# InclinometerDisplay.net
KiCad netlist of a schematic drawn in Altium Designer
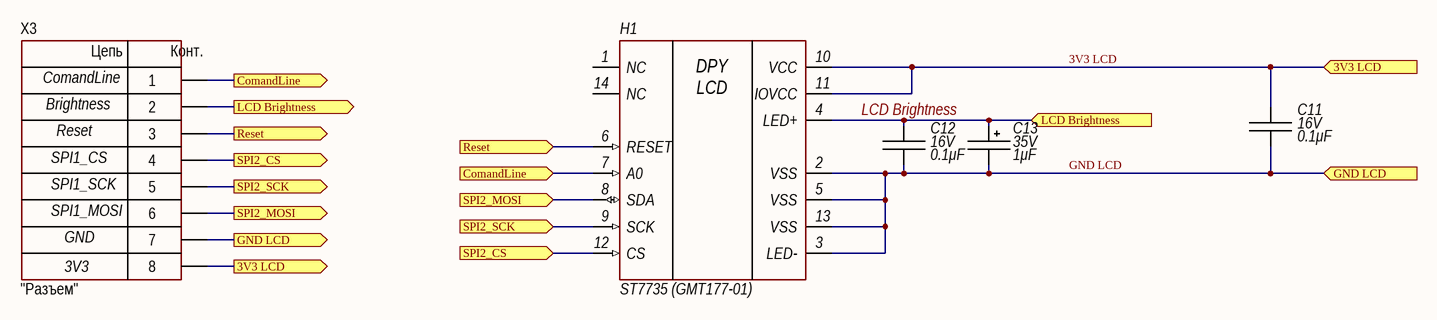
[diagram p0: InclinometerDisplay.SchDoc]

(export (version "E")
  (design (tool "Eeschema 10.0.6"))
  (components
    (comp (ref "C11")
      (value "0.1μF")
      (footprint "CAP: 0603")
      (fields
        (field (name "MANUFACTURER") "Murata Electronics")
        (field (name "PARTNUMBER") "GRM188R71C104KA01D")
        (field (name "VALUEMANUFACTURERPARTNUMBER") "Ceramic capacitor, 0.1μF, X7R, ±10%, 16V, 0603, -55...+125°C")
        (field (name "VOLTAGE") "16V")
      )
      (libsource (lib "Capacitor") (part "Ceramic_0603"))
    )
    (comp (ref "C12")
      (value "0.1μF")
      (footprint "CAP: 0603")
      (fields
        (field (name "MANUFACTURER") "Murata Electronics")
        (field (name "PARTNUMBER") "GRM188R71C104KA01D")
        (field (name "VALUEMANUFACTURERPARTNUMBER") "Ceramic capacitor, 0.1μF, X7R, ±10%, 16V, 0603, -55...+125°C")
        (field (name "VOLTAGE") "16V")
      )
      (libsource (lib "Capacitor") (part "Ceramic_0603"))
    )
    (comp (ref "C13")
      (value "1μF")
      (footprint "CAP: TANTAL-A")
      (fields
        (field (name "MANUFACTURER") "AVX")
        (field (name "PARTNUMBER") "TAJA105K035RNJ")
        (field (name "VALUEMANUFACTURERPARTNUMBER") "Tantalum capacitor, 1μF, 35V, ±10%, 7.5Ohm, case A (3216), -55...+125°C")
        (field (name "VOLTAGE") "35V")
      )
      (libsource (lib "Capacitor") (part "Tantal_A"))
    )
    (comp (ref "H1")
      (value "ST7735 (GMT177-01)")
      (footprint "ST7735 DISPLAY")
      (libsource (lib "Displays") (part "ST7735 DISPLAY"))
    )
    (comp (ref "X3")
      (value "~")
      (footprint "CON: PLS-8")
      (fields
        (field (name "MANUFACTURER") "Connfly")
        (field (name "VALUEMANUFACTURERPARTNUMBER") "Connector, 8pin, 2.54mm, 500VAC, 3A")
        (field (name "PARTNUMBER") "PLS-8")
        (field (name "COMMENTTEXT") "\"Разъем\"")
      )
      (libsource (lib "Connector") (part "PLS-8"))
    )
  )
  (nets
    (net (code "1") (name "/3V3 LCD") (class "Default")
      (node (ref "C11") (pin "2") (pinfunction "2_2") (pintype "power_in"))
      (node (ref "H1") (pin "10") (pinfunction "VCC_10") (pintype "power_in"))
      (node (ref "H1") (pin "11") (pinfunction "IOVCC_11") (pintype "power_in"))
      (node (ref "X3") (pin "8") (pinfunction "8_8") (pintype "power_in"))
    )
    (net (code "2") (name "/ComandLine") (class "Default")
      (node (ref "H1") (pin "7") (pinfunction "A0_7") (pintype "input"))
      (node (ref "X3") (pin "1") (pinfunction "1_1") (pintype "passive"))
    )
    (net (code "3") (name "/GND LCD") (class "Default")
      (node (ref "C11") (pin "1") (pinfunction "1_1") (pintype "power_in"))
      (node (ref "C12") (pin "1") (pinfunction "1_1") (pintype "power_in"))
      (node (ref "C13") (pin "2") (pinfunction "2_2") (pintype "power_in"))
      (node (ref "H1") (pin "13") (pinfunction "VSS_13") (pintype "power_in"))
      (node (ref "H1") (pin "2") (pinfunction "VSS_2") (pintype "power_in"))
      (node (ref "H1") (pin "3") (pinfunction "LED-_3") (pintype "power_in"))
      (node (ref "H1") (pin "5") (pinfunction "VSS_5") (pintype "power_in"))
      (node (ref "X3") (pin "7") (pinfunction "7_7") (pintype "power_in"))
    )
    (net (code "4") (name "/LCD Brightness") (class "Default")
      (node (ref "C12") (pin "2") (pinfunction "2_2") (pintype "power_in"))
      (node (ref "C13") (pin "1") (pinfunction "1_1") (pintype "power_in"))
      (node (ref "H1") (pin "4") (pinfunction "LED+_4") (pintype "power_in"))
      (node (ref "X3") (pin "2") (pinfunction "2_2") (pintype "passive"))
    )
    (net (code "5") (name "/Reset") (class "Default")
      (node (ref "H1") (pin "6") (pinfunction "RESET_6") (pintype "input"))
      (node (ref "X3") (pin "3") (pinfunction "3_3") (pintype "power_in"))
    )
    (net (code "6") (name "/SPI2_CS") (class "Default")
      (node (ref "H1") (pin "12") (pinfunction "CS_12") (pintype "input"))
      (node (ref "X3") (pin "4") (pinfunction "4_4") (pintype "power_in"))
    )
    (net (code "7") (name "/SPI2_MOSI") (class "Default")
      (node (ref "H1") (pin "8") (pinfunction "SDA_8") (pintype "bidirectional"))
      (node (ref "X3") (pin "6") (pinfunction "6_6") (pintype "power_in"))
    )
    (net (code "8") (name "/SPI2_SCK") (class "Default")
      (node (ref "H1") (pin "9") (pinfunction "SCK_9") (pintype "input"))
      (node (ref "X3") (pin "5") (pinfunction "5_5") (pintype "power_in"))
    )
    (net (code "9") (name "unconnected-(H1-NC-Pad1)") (class "Default")
      (node (ref "H1") (pin "1") (pinfunction "NC_1") (pintype "passive"))
    )
    (net (code "10") (name "unconnected-(H1-NC-Pad14)") (class "Default")
      (node (ref "H1") (pin "14") (pinfunction "NC_14") (pintype "passive"))
    )
  )
)
